# CPU.net
KiCad netlist of a schematic drawn in Altium Designer
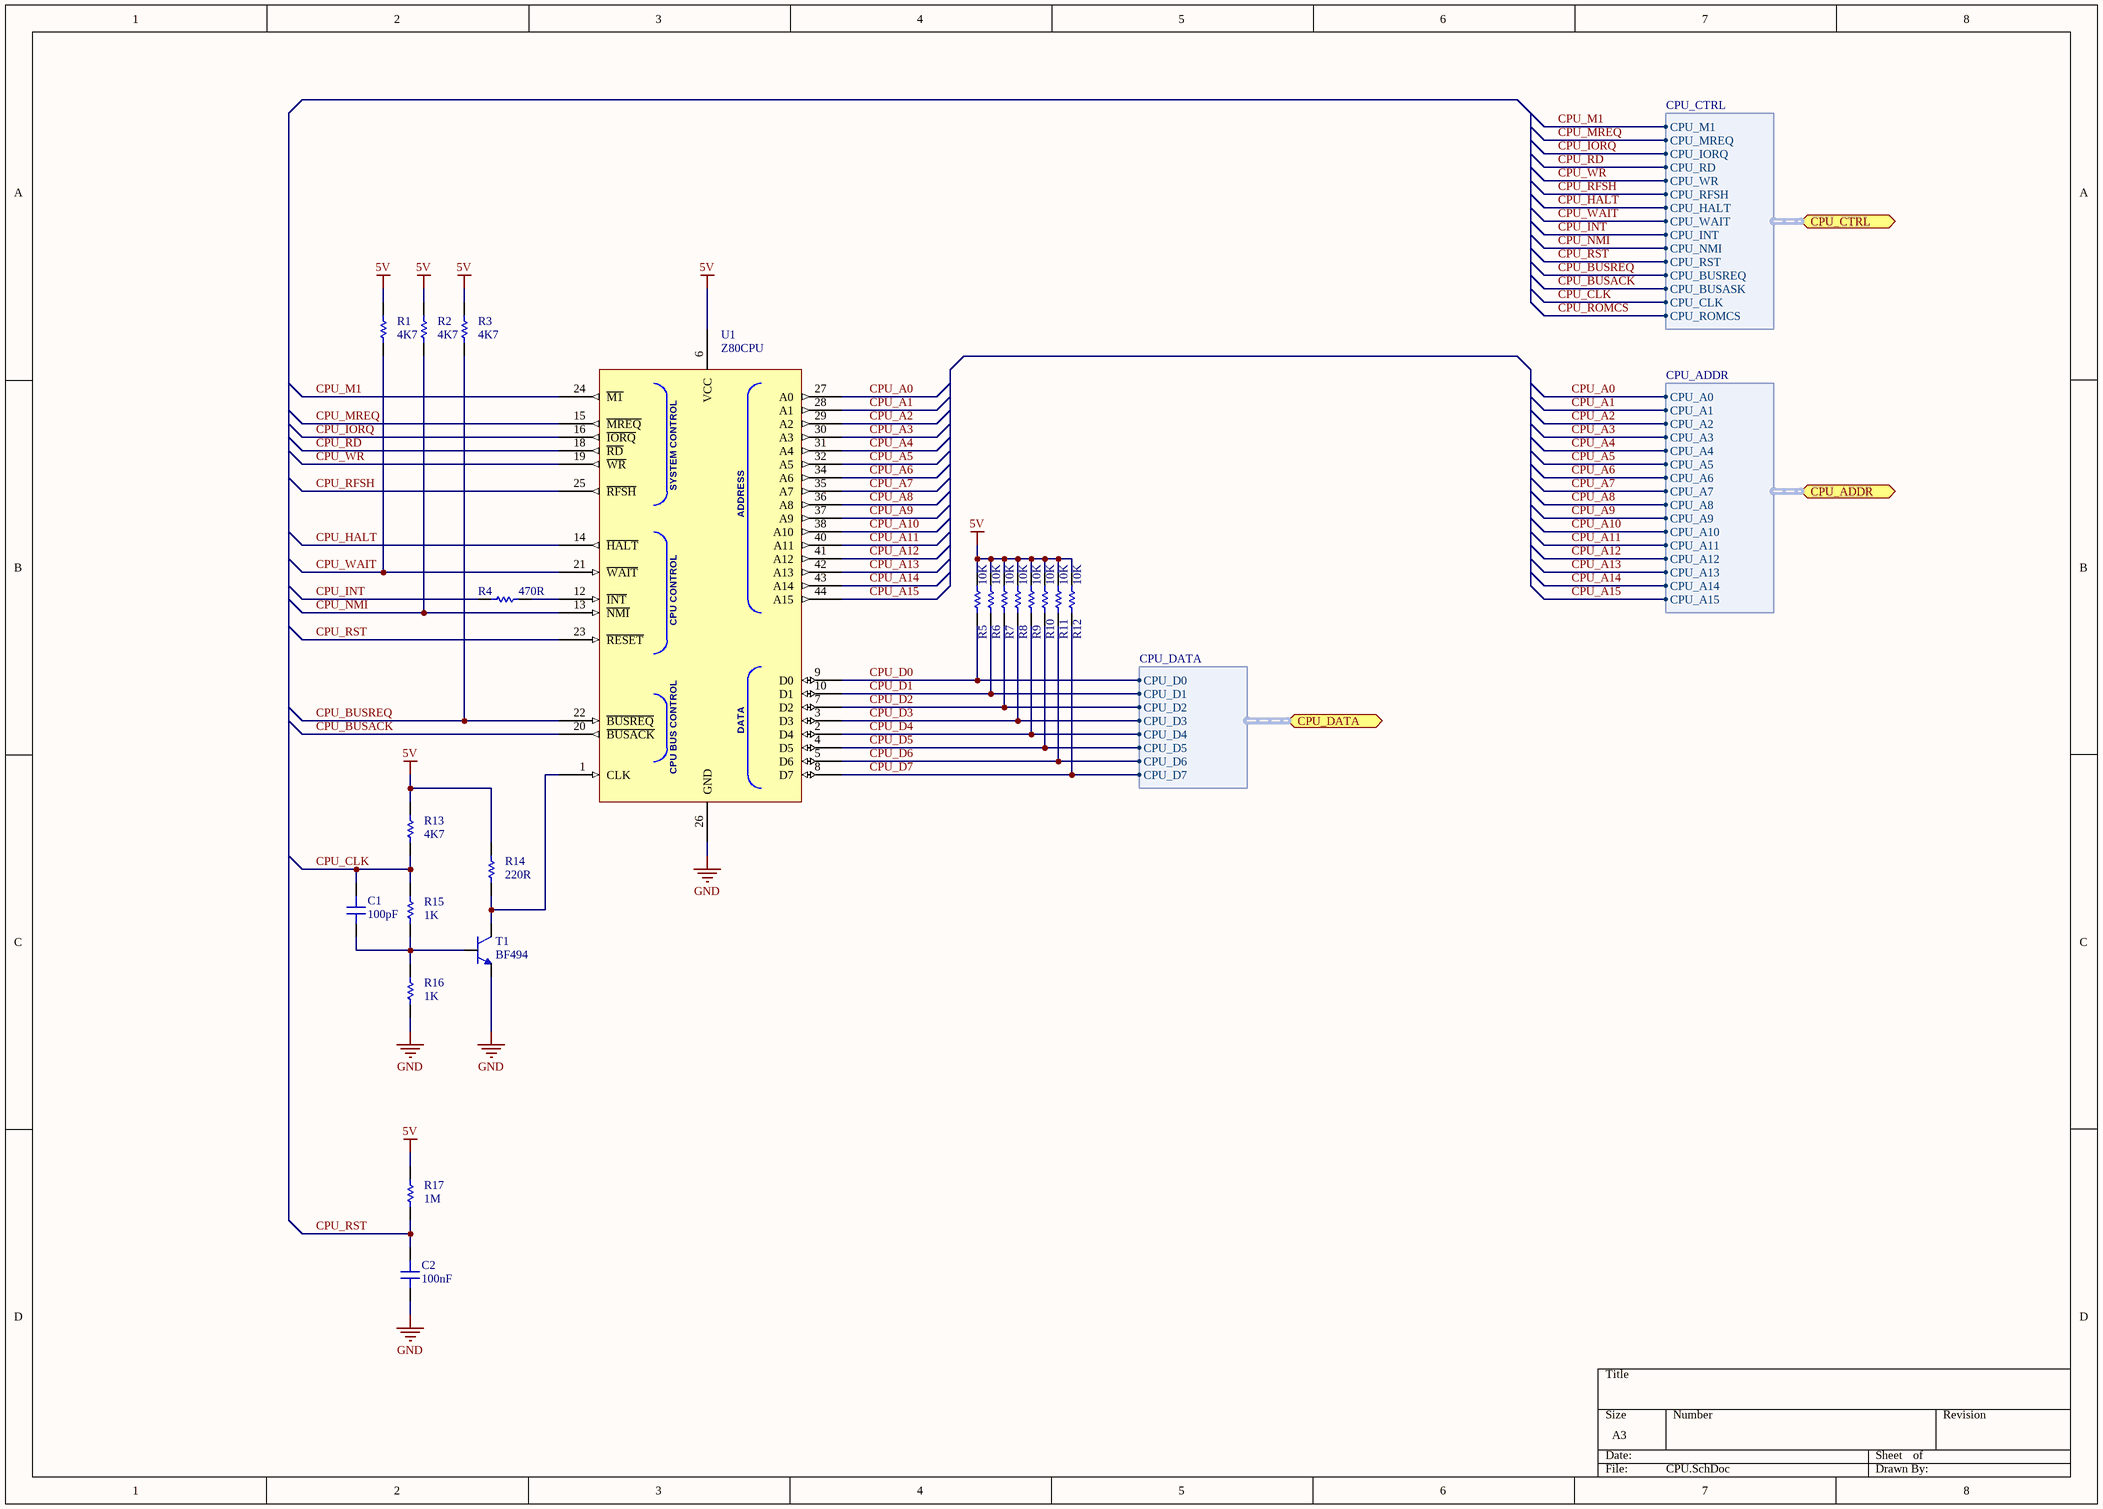
[diagram p0: CPU.SchDoc]

(export (version "E")
  (design (tool "Eeschema 10.0.6"))
  (components
    (comp (ref "C1")
      (value "100pF")
      (footprint "0805")
      (description "Capacitor")
      (libsource (lib "Basic") (part "Capacitor"))
    )
    (comp (ref "C2")
      (value "100nF")
      (footprint "0805")
      (description "Capacitor")
      (libsource (lib "Basic") (part "Capacitor"))
    )
    (comp (ref "R1")
      (value "4K7")
      (footprint "0805")
      (description "Resistor")
      (libsource (lib "Basic") (part "Resistor"))
    )
    (comp (ref "R2")
      (value "4K7")
      (footprint "0805")
      (description "Resistor")
      (libsource (lib "Basic") (part "Resistor"))
    )
    (comp (ref "R3")
      (value "4K7")
      (footprint "0805")
      (description "Resistor")
      (libsource (lib "Basic") (part "Resistor"))
    )
    (comp (ref "R4")
      (value "470R")
      (footprint "0805")
      (description "Resistor")
      (libsource (lib "Basic") (part "Resistor"))
    )
    (comp (ref "R5") (value "10K") (footprint "0805") (libsource (lib "Basic") (part "Resistor")))
    (comp (ref "R6") (value "10K") (footprint "0805") (libsource (lib "Basic") (part "Resistor")))
    (comp (ref "R7") (value "10K") (footprint "0805") (libsource (lib "Basic") (part "Resistor")))
    (comp (ref "R8") (value "10K") (footprint "0805") (libsource (lib "Basic") (part "Resistor")))
    (comp (ref "R9") (value "10K") (footprint "0805") (libsource (lib "Basic") (part "Resistor")))
    (comp (ref "R10") (value "10K") (footprint "0805") (libsource (lib "Basic") (part "Resistor")))
    (comp (ref "R11") (value "10K") (footprint "0805") (libsource (lib "Basic") (part "Resistor")))
    (comp (ref "R12") (value "10K") (footprint "0805") (libsource (lib "Basic") (part "Resistor")))
    (comp (ref "R13")
      (value "4K7")
      (footprint "0805")
      (description "Resistor")
      (libsource (lib "Basic") (part "Resistor"))
    )
    (comp (ref "R14")
      (value "220R")
      (footprint "0805")
      (description "Resistor")
      (libsource (lib "Basic") (part "Resistor"))
    )
    (comp (ref "R15")
      (value "1K")
      (footprint "0805")
      (description "Resistor")
      (libsource (lib "Basic") (part "Resistor"))
    )
    (comp (ref "R16")
      (value "1K")
      (footprint "0805")
      (description "Resistor")
      (libsource (lib "Basic") (part "Resistor"))
    )
    (comp (ref "R17")
      (value "1M")
      (footprint "0805")
      (description "Resistor")
      (libsource (lib "Basic") (part "Resistor"))
    )
    (comp (ref "T1")
      (value "BF494")
      (footprint "TO-92")
      (description "NPN Medium Frequency Transistors")
      (libsource (lib "Basic") (part "BF494"))
    )
    (comp (ref "U1")
      (value "Z80CPU")
      (footprint "Z84C00XXAEG")
      (description "Z80 - CPU")
      (libsource (lib "Zilog") (part "Z84C00xxAEG"))
    )
  )
  (nets
    (net (code "4") (name "/CPU_A0") (class "Default")
      (node (ref "U1") (pin "27") (pinfunction "A0_27") (pintype "output"))
    )
    (net (code "5") (name "/CPU_A1") (class "Default")
      (node (ref "U1") (pin "28") (pinfunction "A1_28") (pintype "output"))
    )
    (net (code "6") (name "/CPU_A2") (class "Default")
      (node (ref "U1") (pin "29") (pinfunction "A2_29") (pintype "output"))
    )
    (net (code "7") (name "/CPU_A3") (class "Default")
      (node (ref "U1") (pin "30") (pinfunction "A3_30") (pintype "output"))
    )
    (net (code "8") (name "/CPU_A4") (class "Default")
      (node (ref "U1") (pin "31") (pinfunction "A4_31") (pintype "output"))
    )
    (net (code "9") (name "/CPU_A5") (class "Default")
      (node (ref "U1") (pin "32") (pinfunction "A5_32") (pintype "output"))
    )
    (net (code "10") (name "/CPU_A6") (class "Default")
      (node (ref "U1") (pin "34") (pinfunction "A6_34") (pintype "output"))
    )
    (net (code "11") (name "/CPU_A7") (class "Default")
      (node (ref "U1") (pin "35") (pinfunction "A7_35") (pintype "output"))
    )
    (net (code "12") (name "/CPU_A8") (class "Default")
      (node (ref "U1") (pin "36") (pinfunction "A8_36") (pintype "output"))
    )
    (net (code "13") (name "/CPU_A9") (class "Default")
      (node (ref "U1") (pin "37") (pinfunction "A9_37") (pintype "output"))
    )
    (net (code "14") (name "/CPU_A10") (class "Default")
      (node (ref "U1") (pin "38") (pinfunction "A10_38") (pintype "output"))
    )
    (net (code "15") (name "/CPU_A11") (class "Default")
      (node (ref "U1") (pin "40") (pinfunction "A11_40") (pintype "output"))
    )
    (net (code "16") (name "/CPU_A12") (class "Default")
      (node (ref "U1") (pin "41") (pinfunction "A12_41") (pintype "output"))
    )
    (net (code "17") (name "/CPU_A13") (class "Default")
      (node (ref "U1") (pin "42") (pinfunction "A13_42") (pintype "output"))
    )
    (net (code "18") (name "/CPU_A14") (class "Default")
      (node (ref "U1") (pin "43") (pinfunction "A14_43") (pintype "output"))
    )
    (net (code "19") (name "/CPU_A15") (class "Default")
      (node (ref "U1") (pin "44") (pinfunction "A15_44") (pintype "output"))
    )
    (net (code "20") (name "/CPU_BUSACK") (class "Default")
      (node (ref "U1") (pin "20") (pinfunction "~{BUSACK}_20") (pintype "output"))
    )
    (net (code "21") (name "/CPU_BUSREQ") (class "Default")
      (node (ref "R3") (pin "1") (pinfunction "1_1") (pintype "passive"))
      (node (ref "U1") (pin "22") (pinfunction "~{BUSREQ}_22") (pintype "input"))
    )
    (net (code "22") (name "/CPU_CLK") (class "Default")
      (node (ref "C1") (pin "2") (pinfunction "2_2") (pintype "passive"))
      (node (ref "R13") (pin "1") (pinfunction "1_1") (pintype "passive"))
      (node (ref "R15") (pin "2") (pinfunction "2_2") (pintype "passive"))
    )
    (net (code "23") (name "/CPU_D0") (class "Default")
      (node (ref "R5") (pin "1") (pinfunction "1_1") (pintype "passive"))
      (node (ref "U1") (pin "9") (pinfunction "D0_9") (pintype "bidirectional"))
    )
    (net (code "24") (name "/CPU_D1") (class "Default")
      (node (ref "R6") (pin "1") (pinfunction "1_1") (pintype "passive"))
      (node (ref "U1") (pin "10") (pinfunction "D1_10") (pintype "bidirectional"))
    )
    (net (code "25") (name "/CPU_D2") (class "Default")
      (node (ref "R7") (pin "1") (pinfunction "1_1") (pintype "passive"))
      (node (ref "U1") (pin "7") (pinfunction "D2_7") (pintype "bidirectional"))
    )
    (net (code "26") (name "/CPU_D3") (class "Default")
      (node (ref "R8") (pin "1") (pinfunction "1_1") (pintype "passive"))
      (node (ref "U1") (pin "3") (pinfunction "D3_3") (pintype "bidirectional"))
    )
    (net (code "27") (name "/CPU_D4") (class "Default")
      (node (ref "R9") (pin "1") (pinfunction "1_1") (pintype "passive"))
      (node (ref "U1") (pin "2") (pinfunction "D4_2") (pintype "bidirectional"))
    )
    (net (code "28") (name "/CPU_D5") (class "Default")
      (node (ref "R10") (pin "1") (pinfunction "1_1") (pintype "passive"))
      (node (ref "U1") (pin "4") (pinfunction "D5_4") (pintype "bidirectional"))
    )
    (net (code "29") (name "/CPU_D6") (class "Default")
      (node (ref "R11") (pin "1") (pinfunction "1_1") (pintype "passive"))
      (node (ref "U1") (pin "5") (pinfunction "D6_5") (pintype "bidirectional"))
    )
    (net (code "30") (name "/CPU_D7") (class "Default")
      (node (ref "R12") (pin "1") (pinfunction "1_1") (pintype "passive"))
      (node (ref "U1") (pin "8") (pinfunction "D7_8") (pintype "bidirectional"))
    )
    (net (code "31") (name "/CPU_HALT") (class "Default")
      (node (ref "U1") (pin "14") (pinfunction "~{HALT}_14") (pintype "output"))
    )
    (net (code "32") (name "/CPU_INT") (class "Default")
      (node (ref "R4") (pin "1") (pinfunction "1_1") (pintype "passive"))
    )
    (net (code "33") (name "/CPU_IORQ") (class "Default")
      (node (ref "U1") (pin "16") (pinfunction "~{IORQ}_16") (pintype "output"))
    )
    (net (code "34") (name "/CPU_M1") (class "Default")
      (node (ref "U1") (pin "24") (pinfunction "~{M1}_24") (pintype "output"))
    )
    (net (code "35") (name "/CPU_MREQ") (class "Default")
      (node (ref "U1") (pin "15") (pinfunction "~{MREQ}_15") (pintype "output"))
    )
    (net (code "36") (name "/CPU_NMI") (class "Default")
      (node (ref "R2") (pin "1") (pinfunction "1_1") (pintype "passive"))
      (node (ref "U1") (pin "13") (pinfunction "~{NMI}_13") (pintype "input"))
    )
    (net (code "37") (name "/CPU_RD") (class "Default")
      (node (ref "U1") (pin "18") (pinfunction "~{RD}_18") (pintype "output"))
    )
    (net (code "38") (name "/CPU_RFSH") (class "Default")
      (node (ref "U1") (pin "25") (pinfunction "~{RFSH}_25") (pintype "output"))
    )
    (net (code "40") (name "/CPU_RST") (class "Default")
      (node (ref "C2") (pin "2") (pinfunction "2_2") (pintype "passive"))
      (node (ref "R17") (pin "1") (pinfunction "1_1") (pintype "passive"))
      (node (ref "U1") (pin "23") (pinfunction "~{RESET}_23") (pintype "input"))
    )
    (net (code "41") (name "/CPU_WAIT") (class "Default")
      (node (ref "R1") (pin "1") (pinfunction "1_1") (pintype "passive"))
      (node (ref "U1") (pin "21") (pinfunction "~{WAIT}_21") (pintype "input"))
    )
    (net (code "42") (name "/CPU_WR") (class "Default")
      (node (ref "U1") (pin "19") (pinfunction "~{WR}_19") (pintype "output"))
    )
    (net (code "46") (name "5V") (class "Default")
      (node (ref "R1") (pin "2") (pinfunction "2_2") (pintype "passive"))
      (node (ref "R10") (pin "2") (pinfunction "2_2") (pintype "passive"))
      (node (ref "R11") (pin "2") (pinfunction "2_2") (pintype "passive"))
      (node (ref "R12") (pin "2") (pinfunction "2_2") (pintype "passive"))
      (node (ref "R13") (pin "2") (pinfunction "2_2") (pintype "passive"))
      (node (ref "R14") (pin "2") (pinfunction "2_2") (pintype "passive"))
      (node (ref "R17") (pin "2") (pinfunction "2_2") (pintype "passive"))
      (node (ref "R2") (pin "2") (pinfunction "2_2") (pintype "passive"))
      (node (ref "R3") (pin "2") (pinfunction "2_2") (pintype "passive"))
      (node (ref "R5") (pin "2") (pinfunction "2_2") (pintype "passive"))
      (node (ref "R6") (pin "2") (pinfunction "2_2") (pintype "passive"))
      (node (ref "R7") (pin "2") (pinfunction "2_2") (pintype "passive"))
      (node (ref "R8") (pin "2") (pinfunction "2_2") (pintype "passive"))
      (node (ref "R9") (pin "2") (pinfunction "2_2") (pintype "passive"))
      (node (ref "U1") (pin "6") (pinfunction "VCC_6") (pintype "power_in"))
    )
    (net (code "47") (name "GND") (class "Default")
      (node (ref "C2") (pin "1") (pinfunction "1_1") (pintype "passive"))
      (node (ref "R16") (pin "1") (pinfunction "1_1") (pintype "passive"))
      (node (ref "T1") (pin "2") (pinfunction "2_2") (pintype "passive"))
      (node (ref "U1") (pin "26") (pinfunction "GND_26") (pintype "power_in"))
    )
    (net (code "48") (name "Net-(C1-Pad1)") (class "Default")
      (node (ref "C1") (pin "1") (pinfunction "1_1") (pintype "passive"))
      (node (ref "R15") (pin "1") (pinfunction "1_1") (pintype "passive"))
      (node (ref "R16") (pin "2") (pinfunction "2_2") (pintype "passive"))
      (node (ref "T1") (pin "1") (pinfunction "1_1") (pintype "passive"))
    )
    (net (code "49") (name "Net-(U1-CLK)") (class "Default")
      (node (ref "R14") (pin "1") (pinfunction "1_1") (pintype "passive"))
      (node (ref "T1") (pin "3") (pinfunction "3_3") (pintype "passive"))
      (node (ref "U1") (pin "1") (pinfunction "CLK_1") (pintype "input"))
    )
    (net (code "50") (name "Net-(U1-~{INT})") (class "Default")
      (node (ref "R4") (pin "2") (pinfunction "2_2") (pintype "passive"))
      (node (ref "U1") (pin "12") (pinfunction "~{INT}_12") (pintype "input"))
    )
    (net (code "51") (name "unconnected-(U1-NC_0-Pad11)") (class "Default")
      (node (ref "U1") (pin "11") (pinfunction "NC_0_11") (pintype "passive"))
    )
    (net (code "52") (name "unconnected-(U1-NC_1-Pad17)") (class "Default")
      (node (ref "U1") (pin "17") (pinfunction "NC_1_17") (pintype "passive"))
    )
    (net (code "53") (name "unconnected-(U1-NC_2-Pad33)") (class "Default")
      (node (ref "U1") (pin "33") (pinfunction "NC_2_33") (pintype "passive"))
    )
    (net (code "54") (name "unconnected-(U1-NC_3-Pad39)") (class "Default")
      (node (ref "U1") (pin "39") (pinfunction "NC_3_39") (pintype "passive"))
    )
  )
)
